# USB.net
KiCad netlist of a schematic drawn in Altium Designer
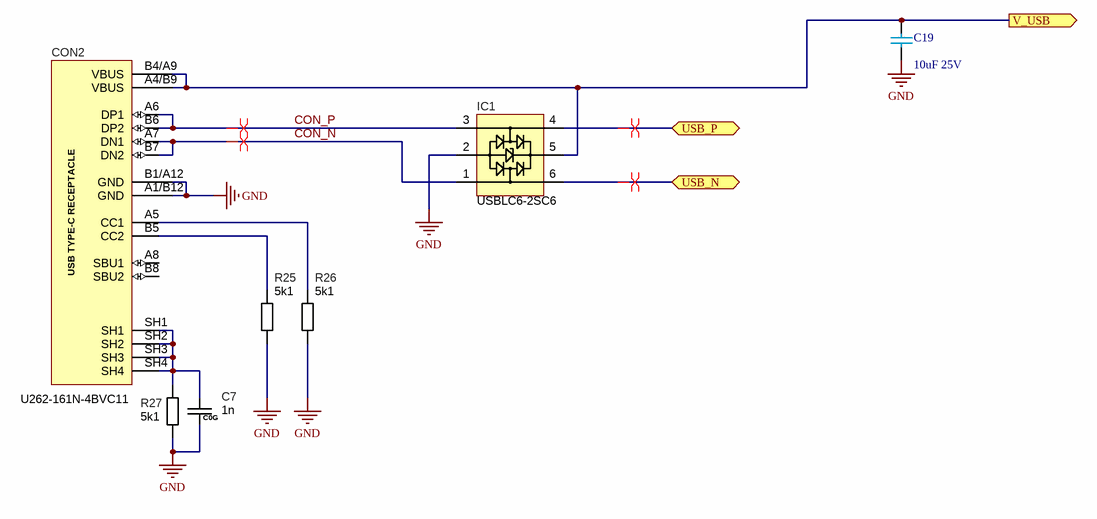
[diagram p0: USB.SchDoc]

(export (version "E")
  (design (tool "Eeschema 10.0.6"))
  (components
    (comp (ref "C7")
      (value "1n")
      (footprint "SMD_PASSIVES:C0603_C0G")
      (description "Precision 0603 C0G/NP0 capacitor footprint")
      (libsource (lib "Passives") (part "C0603_C0G"))
    )
    (comp (ref "C19")
      (value "10uF 25V")
      (footprint "C0603")
      (description "0805, X5R or better")
      (fields (field (name "Comment") "0805"))
      (libsource (lib "Chip_Passives") (part "Cap 10uF 25V"))
    )
    (comp (ref "CON2")
      (value "U262-161N-4BVC11")
      (footprint "USB_C")
      (description "USB C 2.0 connector, SMT, female")
      (libsource (lib "Connectors") (part "USB_C_2.0"))
    )
    (comp (ref "IC1")
      (value "USBLC6-2SC6")
      (footprint "SMD_SEMI:sot23-6")
      (description "USB 2.0 ESD protection")
      (libsource (lib "Discrete Semi") (part "USBLC6-2SC6"))
    )
    (comp (ref "R25")
      (value "5k1")
      (footprint "SMD_PASSIVES:R0603")
      (description "Generic 0603 resistor footprint")
      (libsource (lib "Passives") (part "R0603"))
    )
    (comp (ref "R26")
      (value "5k1")
      (footprint "SMD_PASSIVES:R0603")
      (description "Generic 0603 resistor footprint")
      (libsource (lib "Passives") (part "R0603"))
    )
    (comp (ref "R27")
      (value "5k1")
      (footprint "SMD_PASSIVES:R0603")
      (description "Generic 0603 resistor footprint")
      (libsource (lib "Passives") (part "R0603"))
    )
  )
  (nets
    (net (code "1") (name "/CON_N") (class "Default")
      (node (ref "CON2") (pin "A7") (pinfunction "DN1_A7") (pintype "bidirectional"))
      (node (ref "CON2") (pin "B7") (pinfunction "DN2_B7") (pintype "bidirectional"))
      (node (ref "IC1") (pin "1") (pinfunction "1_1") (pintype "passive"))
    )
    (net (code "2") (name "/CON_P") (class "Default")
      (node (ref "CON2") (pin "A6") (pinfunction "DP1_A6") (pintype "bidirectional"))
      (node (ref "CON2") (pin "B6") (pinfunction "DP2_B6") (pintype "bidirectional"))
      (node (ref "IC1") (pin "3") (pinfunction "3_3") (pintype "passive"))
    )
    (net (code "3") (name "/USB_N") (class "Default")
      (node (ref "IC1") (pin "6") (pinfunction "6_6") (pintype "passive"))
    )
    (net (code "4") (name "/USB_P") (class "Default")
      (node (ref "IC1") (pin "4") (pinfunction "4_4") (pintype "passive"))
    )
    (net (code "5") (name "/V_USB") (class "Default")
      (node (ref "C19") (pin "2") (pinfunction "2_2") (pintype "passive"))
      (node (ref "CON2") (pin "A4/B9") (pinfunction "VBUS_A4/B9") (pintype "power_in"))
      (node (ref "CON2") (pin "B4/A9") (pinfunction "VBUS_B4/A9") (pintype "power_in"))
      (node (ref "IC1") (pin "5") (pinfunction "VBUS_5") (pintype "passive"))
    )
    (net (code "6") (name "GND") (class "Default")
      (node (ref "C19") (pin "1") (pinfunction "1_1") (pintype "passive"))
      (node (ref "C7") (pin "2") (pintype "passive"))
      (node (ref "CON2") (pin "A1/B12") (pinfunction "GND_A1/B12") (pintype "power_in"))
      (node (ref "CON2") (pin "B1/A12") (pinfunction "GND_B1/A12") (pintype "power_in"))
      (node (ref "IC1") (pin "2") (pinfunction "GND_2") (pintype "passive"))
      (node (ref "R25") (pin "2") (pinfunction "2_2") (pintype "passive"))
      (node (ref "R26") (pin "2") (pinfunction "2_2") (pintype "passive"))
      (node (ref "R27") (pin "2") (pinfunction "2_2") (pintype "passive"))
    )
    (net (code "7") (name "Net-(C7-Pad1)") (class "Default")
      (node (ref "C7") (pin "1") (pintype "passive"))
      (node (ref "CON2") (pin "SH1") (pinfunction "SH1_SH1") (pintype "power_in"))
      (node (ref "CON2") (pin "SH2") (pinfunction "SH2_SH2") (pintype "power_in"))
      (node (ref "CON2") (pin "SH3") (pinfunction "SH3_SH3") (pintype "power_in"))
      (node (ref "CON2") (pin "SH4") (pinfunction "SH4_SH4") (pintype "power_in"))
      (node (ref "R27") (pin "1") (pinfunction "1_1") (pintype "passive"))
    )
    (net (code "8") (name "Net-(CON2-CC1)") (class "Default")
      (node (ref "CON2") (pin "A5") (pinfunction "CC1_A5") (pintype "passive"))
      (node (ref "R26") (pin "1") (pinfunction "1_1") (pintype "passive"))
    )
    (net (code "9") (name "Net-(CON2-CC2)") (class "Default")
      (node (ref "CON2") (pin "B5") (pinfunction "CC2_B5") (pintype "passive"))
      (node (ref "R25") (pin "1") (pinfunction "1_1") (pintype "passive"))
    )
    (net (code "10") (name "unconnected-(CON2-SBU1-PadA8)") (class "Default")
      (node (ref "CON2") (pin "A8") (pinfunction "SBU1_A8") (pintype "bidirectional"))
    )
    (net (code "11") (name "unconnected-(CON2-SBU2-PadB8)") (class "Default")
      (node (ref "CON2") (pin "B8") (pinfunction "SBU2_B8") (pintype "bidirectional"))
    )
  )
)
